# GPS.net
KiCad netlist of a schematic drawn in Altium Designer
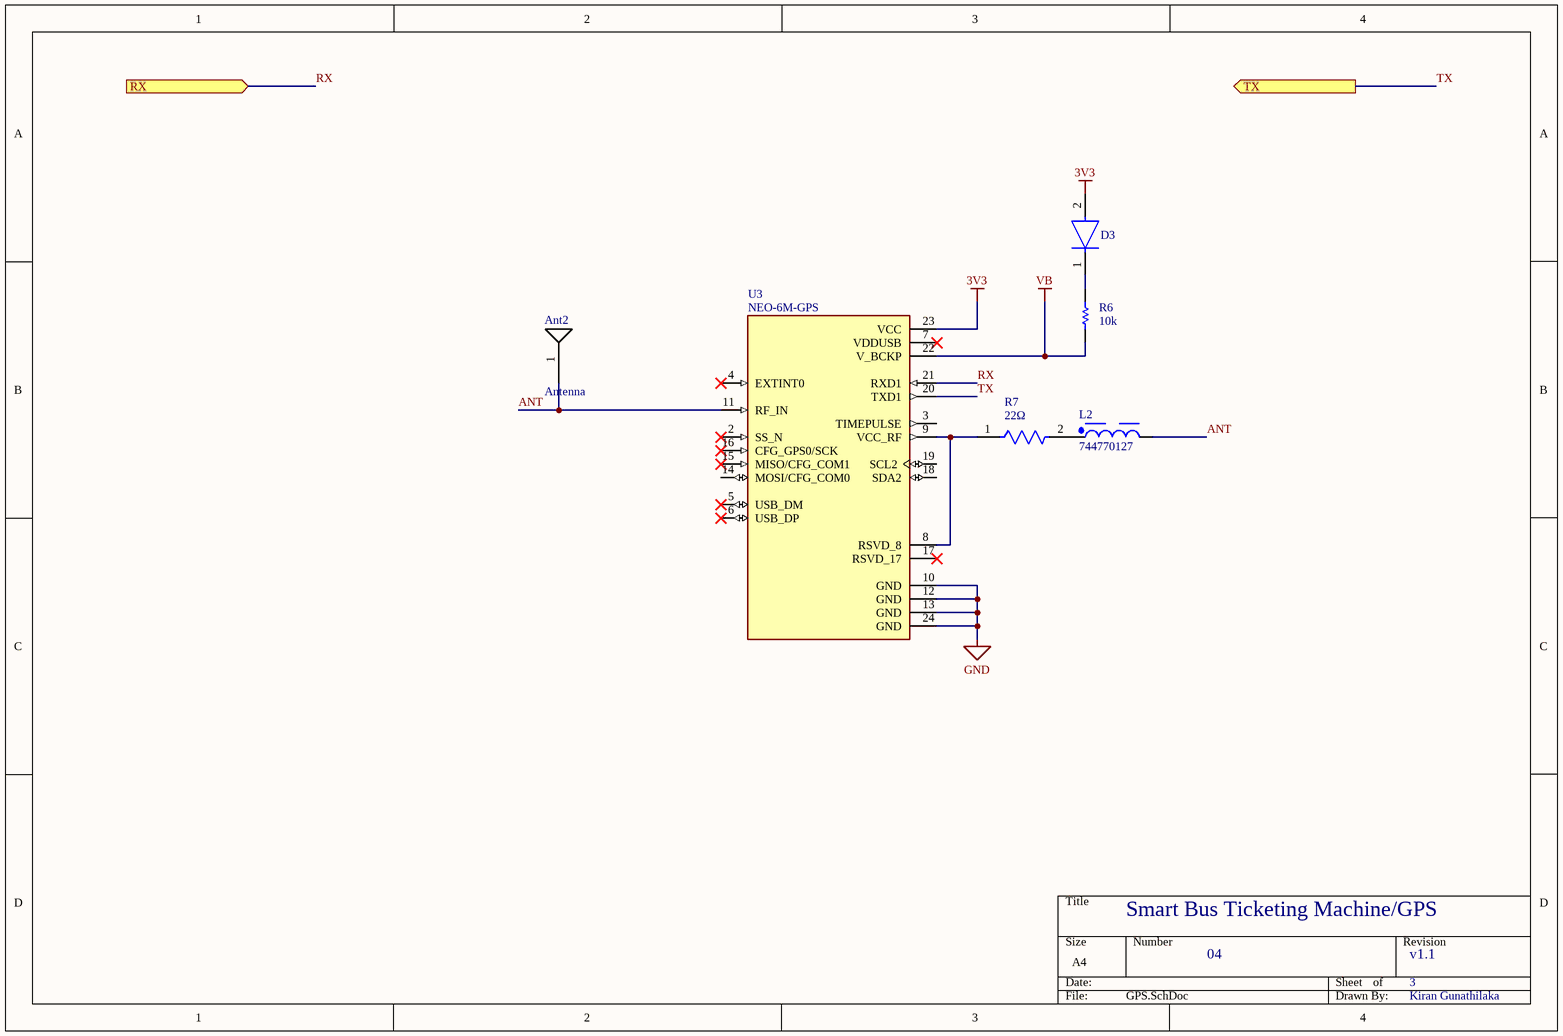
[diagram p0: GPS.SchDoc]

(export (version "E")
  (design (tool "Eeschema 10.0.6"))
  (components
    (comp (ref "Ant2") (value "Antenna") (footprint "Antenna") (libsource (lib "Schlib1") (part "Antenna")))
    (comp (ref "D3")
      (value "TS4148 RYG")
      (footprint "FP-TS4148_RYG-MFG")
      (description "Rectifier Diode Switching 75V 0.15A 4ns 2-Pin Case 0805(2012Metric) T/R")
      (libsource (lib "Altium Content Vault") (part "d7152d700b627762746794eb795d46e"))
    )
    (comp (ref "L2")
      (value "744770127")
      (footprint "WE-PD_1280")
      (fields (field (name "TOLERANCE") "20%"))
      (libsource (lib "Altium Content Vault") (part "Inductor - 2"))
    )
    (comp (ref "R6")
      (value "10k")
      (footprint "RESC2013X60X35NL10T20")
      (description "Chip Resistor, 10 KOhm, +/- 1%, 0.125 W, -55 to 155 degC, 0805 (2012 Metric), RoHS, Tape and Reel")
      (fields (field (name "MANUFACTURER") "Yageo") (field (name "Comment") "RC0805FR-0710KL"))
      (libsource (lib "Altium Content Vault") (part "RES-2"))
    )
    (comp (ref "R7")
      (value "22Ω")
      (footprint "FP-CRGCQ0805-IPC_C")
      (description "CRGCQ 0805 22R 1%")
      (fields
        (field (name "TOLERANCE") "0.01")
        (field (name "OCTOPART") "https://octopart.com/crgcq0805f22r-te+connectivity-91018162")
      )
      (libsource (lib "Altium Content Vault") (part "1029c3af85768c4190bb7ad29bc67b5"))
    )
    (comp (ref "U3")
      (value "NEO-6M-GPS")
      (footprint "XCVR_NEO-6M-GPS")
      (description "GPS Development Tools SparkFun GNSS-RTK Dead Reckoning Breakout - ZED-F9K (Qwiic)")
      (fields (field (name "MF") "u-blox"))
      (libsource (lib "Schlib1") (part "NEO-6M-GPS"))
    )
  )
  (nets
    (net (code "1") (name "/ANT") (class "Default")
      (node (ref "Ant2") (pin "1") (pintype "passive"))
      (node (ref "L2") (pin "2") (pinfunction "2_2") (pintype "passive"))
      (node (ref "U3") (pin "11") (pinfunction "RF_IN_11") (pintype "input"))
    )
    (net (code "2") (name "/RX") (class "Default")
      (node (ref "U3") (pin "21") (pinfunction "RXD1_21") (pintype "input"))
    )
    (net (code "3") (name "/TX") (class "Default")
      (node (ref "U3") (pin "20") (pinfunction "TXD1_20") (pintype "output"))
    )
    (net (code "4") (name "3V3") (class "Default")
      (node (ref "D3") (pin "2") (pinfunction "A_2") (pintype "passive"))
      (node (ref "U3") (pin "23") (pinfunction "VCC_23") (pintype "passive"))
    )
    (net (code "5") (name "GND") (class "Default")
      (node (ref "U3") (pin "10") (pinfunction "GND_10") (pintype "passive"))
      (node (ref "U3") (pin "12") (pinfunction "GND_12") (pintype "passive"))
      (node (ref "U3") (pin "13") (pinfunction "GND_13") (pintype "passive"))
      (node (ref "U3") (pin "24") (pinfunction "GND_24") (pintype "passive"))
    )
    (net (code "6") (name "Net-(D3-C)") (class "Default")
      (node (ref "D3") (pin "1") (pinfunction "C_1") (pintype "passive"))
      (node (ref "R6") (pin "2") (pinfunction "2_2") (pintype "passive"))
    )
    (net (code "7") (name "Net-(L2-Pad1)") (class "Default")
      (node (ref "L2") (pin "1") (pinfunction "1_1") (pintype "passive"))
      (node (ref "R7") (pin "2") (pinfunction "2_2") (pintype "passive"))
    )
    (net (code "8") (name "Net-(U3-RSVD_8)") (class "Default")
      (node (ref "R7") (pin "1") (pinfunction "1_1") (pintype "passive"))
      (node (ref "U3") (pin "8") (pinfunction "RSVD_8_8") (pintype "passive"))
      (node (ref "U3") (pin "9") (pinfunction "VCC_RF_9") (pintype "output"))
    )
    (net (code "9") (name "VB") (class "Default")
      (node (ref "R6") (pin "1") (pinfunction "1_1") (pintype "passive"))
      (node (ref "U3") (pin "22") (pinfunction "V_BCKP_22") (pintype "passive"))
    )
    (net (code "10") (name "unconnected-(U3-CFG_GPS0{slash}SCK-Pad16)") (class "Default")
      (node (ref "U3") (pin "16") (pinfunction "CFG_GPS0/SCK_16") (pintype "input+no_connect"))
    )
    (net (code "11") (name "unconnected-(U3-EXTINT0-Pad4)") (class "Default")
      (node (ref "U3") (pin "4") (pinfunction "EXTINT0_4") (pintype "input+no_connect"))
    )
    (net (code "12") (name "unconnected-(U3-MISO{slash}CFG_COM1-Pad15)") (class "Default")
      (node (ref "U3") (pin "15") (pinfunction "MISO/CFG_COM1_15") (pintype "input+no_connect"))
    )
    (net (code "13") (name "unconnected-(U3-MOSI{slash}CFG_COM0-Pad14)") (class "Default")
      (node (ref "U3") (pin "14") (pinfunction "MOSI/CFG_COM0_14") (pintype "bidirectional"))
    )
    (net (code "14") (name "unconnected-(U3-RSVD_17-Pad17)") (class "Default")
      (node (ref "U3") (pin "17") (pinfunction "RSVD_17_17") (pintype "passive+no_connect"))
    )
    (net (code "15") (name "unconnected-(U3-SCL2-Pad19)") (class "Default")
      (node (ref "U3") (pin "19") (pinfunction "SCL2_19") (pintype "bidirectional"))
    )
    (net (code "16") (name "unconnected-(U3-SDA2-Pad18)") (class "Default")
      (node (ref "U3") (pin "18") (pinfunction "SDA2_18") (pintype "bidirectional"))
    )
    (net (code "17") (name "unconnected-(U3-SS_N-Pad2)") (class "Default")
      (node (ref "U3") (pin "2") (pinfunction "SS_N_2") (pintype "input+no_connect"))
    )
    (net (code "18") (name "unconnected-(U3-TIMEPULSE-Pad3)") (class "Default")
      (node (ref "U3") (pin "3") (pinfunction "TIMEPULSE_3") (pintype "output"))
    )
    (net (code "19") (name "unconnected-(U3-USB_DM-Pad5)") (class "Default")
      (node (ref "U3") (pin "5") (pinfunction "USB_DM_5") (pintype "bidirectional+no_connect"))
    )
    (net (code "20") (name "unconnected-(U3-USB_DP-Pad6)") (class "Default")
      (node (ref "U3") (pin "6") (pinfunction "USB_DP_6") (pintype "bidirectional+no_connect"))
    )
    (net (code "21") (name "unconnected-(U3-VDDUSB-Pad7)") (class "Default")
      (node (ref "U3") (pin "7") (pinfunction "VDDUSB_7") (pintype "passive+no_connect"))
    )
  )
)
